# Column.net
KiCad netlist of a schematic drawn in Altium Designer
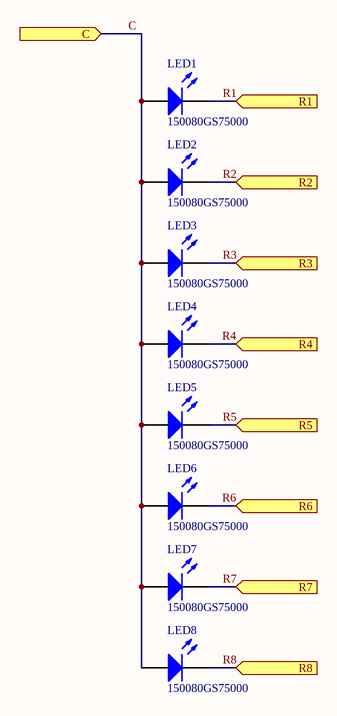
[diagram p0: Column.SchDoc]

(export (version "E")
  (design (tool "Eeschema 10.0.6"))
  (components
    (comp (ref "LED1")
      (value "150080GS75000")
      (footprint "0805_A")
      (description "SMD mono-color Chip LED, WL-SMCW, Green")
      (libsource (lib "WL-SMCW SMD chip LED top view mono-color waterclear") (part "150080GS75000"))
    )
    (comp (ref "LED2")
      (value "150080GS75000")
      (footprint "0805_A")
      (description "SMD mono-color Chip LED, WL-SMCW, Green")
      (libsource (lib "WL-SMCW SMD chip LED top view mono-color waterclear") (part "150080GS75000"))
    )
    (comp (ref "LED3")
      (value "150080GS75000")
      (footprint "0805_A")
      (description "SMD mono-color Chip LED, WL-SMCW, Green")
      (libsource (lib "WL-SMCW SMD chip LED top view mono-color waterclear") (part "150080GS75000"))
    )
    (comp (ref "LED4")
      (value "150080GS75000")
      (footprint "0805_A")
      (description "SMD mono-color Chip LED, WL-SMCW, Green")
      (libsource (lib "WL-SMCW SMD chip LED top view mono-color waterclear") (part "150080GS75000"))
    )
    (comp (ref "LED5")
      (value "150080GS75000")
      (footprint "0805_A")
      (description "SMD mono-color Chip LED, WL-SMCW, Green")
      (libsource (lib "WL-SMCW SMD chip LED top view mono-color waterclear") (part "150080GS75000"))
    )
    (comp (ref "LED6")
      (value "150080GS75000")
      (footprint "0805_A")
      (description "SMD mono-color Chip LED, WL-SMCW, Green")
      (libsource (lib "WL-SMCW SMD chip LED top view mono-color waterclear") (part "150080GS75000"))
    )
    (comp (ref "LED7")
      (value "150080GS75000")
      (footprint "0805_A")
      (description "SMD mono-color Chip LED, WL-SMCW, Green")
      (libsource (lib "WL-SMCW SMD chip LED top view mono-color waterclear") (part "150080GS75000"))
    )
    (comp (ref "LED8")
      (value "150080GS75000")
      (footprint "0805_A")
      (description "SMD mono-color Chip LED, WL-SMCW, Green")
      (libsource (lib "WL-SMCW SMD chip LED top view mono-color waterclear") (part "150080GS75000"))
    )
  )
  (nets
    (net (code "1") (name "/C") (class "Default")
      (node (ref "LED1") (pin "2") (pinfunction "A_2") (pintype "passive"))
      (node (ref "LED2") (pin "2") (pinfunction "A_2") (pintype "passive"))
      (node (ref "LED3") (pin "2") (pinfunction "A_2") (pintype "passive"))
      (node (ref "LED4") (pin "2") (pinfunction "A_2") (pintype "passive"))
      (node (ref "LED5") (pin "2") (pinfunction "A_2") (pintype "passive"))
      (node (ref "LED6") (pin "2") (pinfunction "A_2") (pintype "passive"))
      (node (ref "LED7") (pin "2") (pinfunction "A_2") (pintype "passive"))
      (node (ref "LED8") (pin "2") (pinfunction "A_2") (pintype "passive"))
    )
    (net (code "2") (name "/R1") (class "Default")
      (node (ref "LED1") (pin "1") (pinfunction "K_1") (pintype "passive"))
    )
    (net (code "3") (name "/R2") (class "Default")
      (node (ref "LED2") (pin "1") (pinfunction "K_1") (pintype "passive"))
    )
    (net (code "4") (name "/R3") (class "Default")
      (node (ref "LED3") (pin "1") (pinfunction "K_1") (pintype "passive"))
    )
    (net (code "5") (name "/R4") (class "Default")
      (node (ref "LED4") (pin "1") (pinfunction "K_1") (pintype "passive"))
    )
    (net (code "6") (name "/R5") (class "Default")
      (node (ref "LED5") (pin "1") (pinfunction "K_1") (pintype "passive"))
    )
    (net (code "7") (name "/R6") (class "Default")
      (node (ref "LED6") (pin "1") (pinfunction "K_1") (pintype "passive"))
    )
    (net (code "8") (name "/R7") (class "Default")
      (node (ref "LED7") (pin "1") (pinfunction "K_1") (pintype "passive"))
    )
    (net (code "9") (name "/R8") (class "Default")
      (node (ref "LED8") (pin "1") (pinfunction "K_1") (pintype "passive"))
    )
  )
)
